# PT100.net
KiCad netlist of a schematic drawn in Altium Designer
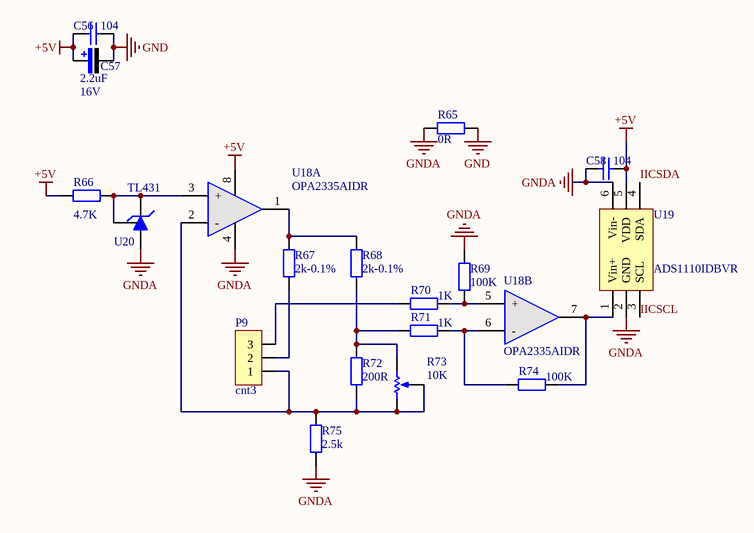
[diagram p0: PT100检测电路.SchDoc]

(export (version "E")
  (design (tool "Eeschema 10.0.6"))
  (components
    (comp (ref "C56")
      (value "104")
      (footprint "C-RAD-0603")
      (description "无极性电容")
      (fields (field (name "Comment") "Cap") (field (name "PUBLISHER") "Altium Limited"))
      (libsource (lib "Fszhang") (part "Cap"))
    )
    (comp (ref "C57")
      (value "2.2uF")
      (footprint "CAP-3216")
      (description "极性电解电容")
      (fields
        (field (name "VOL") "16V")
        (field (name "Comment") "Cap Pol")
        (field (name "PUBLISHER") "Altium Limited")
      )
      (libsource (lib "Fszhang") (part "Cap Pol"))
    )
    (comp (ref "C58")
      (value "104")
      (footprint "C-RAD-0603")
      (description "无极性电容")
      (fields (field (name "Comment") "Cap") (field (name "PUBLISHER") "Altium Limited"))
      (libsource (lib "Fszhang") (part "Cap"))
    )
    (comp (ref "P9")
      (value "cnt3")
      (footprint "7.62mmPCB接线端子3p")
      (description "3p接线端子")
      (libsource (lib "MY_Library") (part "cnt3"))
    )
    (comp (ref "R65")
      (value "0R")
      (footprint "0603-1")
      (description "贴片电阻")
      (fields (field (name "Comment") "Res1") (field (name "PUBLISHER") "Altium Limited"))
      (libsource (lib "") (part "Res1_2"))
    )
    (comp (ref "R66")
      (value "4.7K")
      (footprint "0603-1")
      (description "贴片电阻")
      (fields (field (name "Comment") "Res1") (field (name "PUBLISHER") "Altium Limited"))
      (libsource (lib "") (part "Res1_1"))
    )
    (comp (ref "R67")
      (value "2k-0.1%")
      (footprint "0603-1")
      (description "贴片电阻")
      (fields (field (name "Comment") "Res1") (field (name "PUBLISHER") "Altium Limited"))
      (libsource (lib "Fszhang") (part "Res1"))
    )
    (comp (ref "R68")
      (value "2k-0.1%")
      (footprint "0603-1")
      (description "贴片电阻")
      (fields (field (name "Comment") "Res1") (field (name "PUBLISHER") "Altium Limited"))
      (libsource (lib "Fszhang") (part "Res1"))
    )
    (comp (ref "R69")
      (value "100K")
      (footprint "0603-1")
      (description "贴片电阻")
      (fields (field (name "Comment") "Res1") (field (name "PUBLISHER") "Altium Limited"))
      (libsource (lib "Fszhang") (part "Res1"))
    )
    (comp (ref "R70")
      (value "1K")
      (footprint "0603-1")
      (description "贴片电阻")
      (fields (field (name "Comment") "Res1") (field (name "PUBLISHER") "Altium Limited"))
      (libsource (lib "") (part "Res1_1"))
    )
    (comp (ref "R71")
      (value "1K")
      (footprint "0603-1")
      (description "贴片电阻")
      (fields (field (name "Comment") "Res1") (field (name "PUBLISHER") "Altium Limited"))
      (libsource (lib "") (part "Res1_1"))
    )
    (comp (ref "R72")
      (value "200R")
      (footprint "0603-1")
      (description "贴片电阻")
      (fields (field (name "Comment") "Res1") (field (name "PUBLISHER") "Altium Limited"))
      (libsource (lib "Fszhang") (part "Res1"))
    )
    (comp (ref "R73")
      (value "10K")
      (footprint "VR-3266W")
      (description "精密可调电阻")
      (fields (field (name "Comment") "RPot") (field (name "PUBLISHER") "Altium Limited"))
      (libsource (lib "Fszhang") (part "RPot"))
    )
    (comp (ref "R74")
      (value "100K")
      (footprint "0603-1")
      (description "贴片电阻")
      (fields (field (name "Comment") "Res1") (field (name "PUBLISHER") "Altium Limited"))
      (libsource (lib "") (part "Res1_1"))
    )
    (comp (ref "R75")
      (value "2.5k")
      (footprint "0603-1")
      (description "贴片电阻")
      (fields (field (name "Comment") "Res1") (field (name "PUBLISHER") "Altium Limited"))
      (libsource (lib "Fszhang") (part "Res1"))
    )
    (comp (ref "U18")
      (value "OPA2335AIDR")
      (footprint "NSO8_N")
      (description "双运放")
      (libsource (lib "Fszhang") (part "AD8667"))
    )
    (comp (ref "U19")
      (value "ADS1110IDBVR")
      (footprint "SOT23-6")
      (description "16位内部基准AD芯片IIC")
      (libsource (lib "Fszhang") (part "ADS1110IDBVR"))
    )
    (comp (ref "U20") (value "TL431") (footprint "SOT23") (libsource (lib "MY_Library") (part "TL431")))
  )
  (nets
    (net (code "1") (name "+5V") (class "Default")
      (node (ref "C56") (pin "1") (pinfunction "1_1") (pintype "passive"))
      (node (ref "C57") (pin "1") (pinfunction "1_1") (pintype "passive"))
      (node (ref "C58") (pin "2") (pinfunction "2_2") (pintype "passive"))
      (node (ref "R66") (pin "1") (pinfunction "1_1") (pintype "passive"))
      (node (ref "U18") (pin "8") (pinfunction "V+_8") (pintype "power_in"))
      (node (ref "U19") (pin "5") (pinfunction "VDD_5") (pintype "passive"))
    )
    (net (code "2") (name "/IICSCL") (class "Default")
      (node (ref "U19") (pin "3") (pinfunction "SCL_3") (pintype "passive"))
    )
    (net (code "3") (name "/IICSDA") (class "Default")
      (node (ref "U19") (pin "4") (pinfunction "SDA_4") (pintype "passive"))
    )
    (net (code "4") (name "GND") (class "Default")
      (node (ref "C56") (pin "2") (pinfunction "2_2") (pintype "passive"))
      (node (ref "C57") (pin "2") (pinfunction "2_2") (pintype "passive"))
      (node (ref "R65") (pin "1") (pinfunction "1_1") (pintype "passive"))
    )
    (net (code "5") (name "GNDA") (class "Default")
      (node (ref "C58") (pin "1") (pinfunction "1_1") (pintype "passive"))
      (node (ref "R65") (pin "2") (pinfunction "2_2") (pintype "passive"))
      (node (ref "R69") (pin "2") (pinfunction "2_2") (pintype "passive"))
      (node (ref "R75") (pin "1") (pinfunction "1_1") (pintype "passive"))
      (node (ref "U18") (pin "4") (pinfunction "V-_4") (pintype "power_in"))
      (node (ref "U19") (pin "2") (pinfunction "GND_2") (pintype "passive"))
      (node (ref "U19") (pin "6") (pinfunction "Vin-_6") (pintype "passive"))
      (node (ref "U20") (pin "3") (pinfunction "3_3") (pintype "passive"))
    )
    (net (code "6") (name "Net-(P9-Pad2)") (class "Default")
      (node (ref "P9") (pin "2") (pinfunction "2_2") (pintype "passive"))
      (node (ref "R67") (pin "1") (pinfunction "1_1") (pintype "passive"))
    )
    (net (code "7") (name "Net-(P9-Pad3)") (class "Default")
      (node (ref "P9") (pin "3") (pinfunction "3_3") (pintype "passive"))
      (node (ref "R70") (pin "1") (pinfunction "1_1") (pintype "passive"))
    )
    (net (code "8") (name "Net-(R73-BOT)") (class "Default")
      (node (ref "R68") (pin "1") (pinfunction "1_1") (pintype "passive"))
      (node (ref "R71") (pin "1") (pinfunction "1_1") (pintype "passive"))
      (node (ref "R72") (pin "2") (pinfunction "2_2") (pintype "passive"))
      (node (ref "R73") (pin "3") (pinfunction "BOT_3") (pintype "passive"))
    )
    (net (code "9") (name "Net-(R73-TAP)") (class "Default")
      (node (ref "P9") (pin "1") (pinfunction "1_1") (pintype "passive"))
      (node (ref "R72") (pin "1") (pinfunction "1_1") (pintype "passive"))
      (node (ref "R73") (pin "1") (pinfunction "TOP_1") (pintype "passive"))
      (node (ref "R73") (pin "2") (pinfunction "TAP_2") (pintype "passive"))
      (node (ref "R75") (pin "2") (pinfunction "2_2") (pintype "passive"))
      (node (ref "U18") (pin "2") (pinfunction "-_2") (pintype "passive"))
    )
    (net (code "10") (name "Net-(U18A-+)") (class "Default")
      (node (ref "R66") (pin "2") (pinfunction "2_2") (pintype "passive"))
      (node (ref "U18") (pin "3") (pinfunction "+_3") (pintype "passive"))
      (node (ref "U20") (pin "1") (pinfunction "1_1") (pintype "passive"))
      (node (ref "U20") (pin "2") (pinfunction "2_2") (pintype "passive"))
    )
    (net (code "11") (name "Net-(U18A-OUT1)") (class "Default")
      (node (ref "R67") (pin "2") (pinfunction "2_2") (pintype "passive"))
      (node (ref "R68") (pin "2") (pinfunction "2_2") (pintype "passive"))
      (node (ref "U18") (pin "1") (pinfunction "OUT1_1") (pintype "passive"))
    )
    (net (code "12") (name "Net-(U18B-+)") (class "Default")
      (node (ref "R69") (pin "1") (pinfunction "1_1") (pintype "passive"))
      (node (ref "R70") (pin "2") (pinfunction "2_2") (pintype "passive"))
      (node (ref "U18") (pin "5") (pinfunction "+_5") (pintype "passive"))
    )
    (net (code "13") (name "Net-(U18B--)") (class "Default")
      (node (ref "R71") (pin "2") (pinfunction "2_2") (pintype "passive"))
      (node (ref "R74") (pin "1") (pinfunction "1_1") (pintype "passive"))
      (node (ref "U18") (pin "6") (pinfunction "-_6") (pintype "passive"))
    )
    (net (code "14") (name "Net-(U18B-OUT2)") (class "Default")
      (node (ref "R74") (pin "2") (pinfunction "2_2") (pintype "passive"))
      (node (ref "U18") (pin "7") (pinfunction "OUT2_7") (pintype "passive"))
      (node (ref "U19") (pin "1") (pinfunction "Vin+_1") (pintype "passive"))
    )
  )
)
